# design.net
KiCad netlist of a schematic drawn in Altium Designer
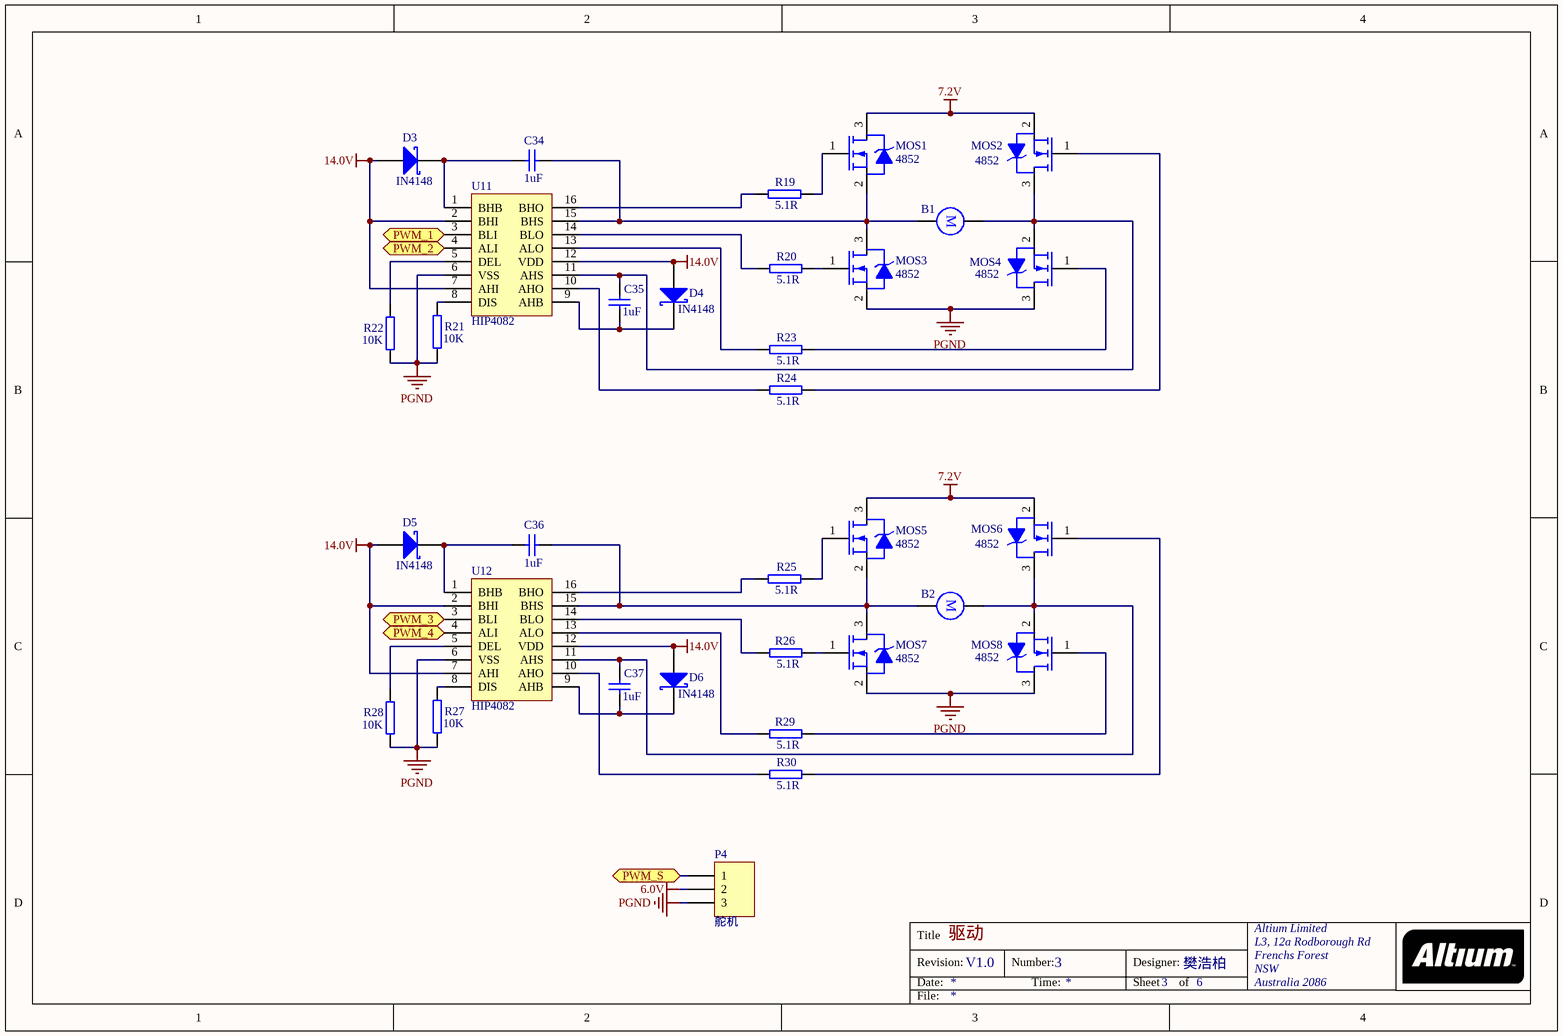
[diagram p0: 驱动.SchDoc]

(export (version "E")
  (design (tool "Eeschema 10.0.6"))
  (components
    (comp (ref "B1")
      (value "Motor")
      (footprint "Header-5.0-SMD")
      (fields (field (name "PUBLISHER") "Altium Limited"))
      (libsource (lib "Connectors") (part "Motor"))
    )
    (comp (ref "B2")
      (value "Motor")
      (footprint "Header-5.0-SMD")
      (fields (field (name "PUBLISHER") "Altium Limited"))
      (libsource (lib "Connectors") (part "Motor"))
    )
    (comp (ref "C34") (value "1uF") (footprint "CAP-0603") (libsource (lib "Connectors") (part "Cap")))
    (comp (ref "C35") (value "1uF") (footprint "CAP-0603") (libsource (lib "Connectors") (part "Cap")))
    (comp (ref "C36") (value "1uF") (footprint "CAP-0603") (libsource (lib "Connectors") (part "Cap")))
    (comp (ref "C37") (value "1uF") (footprint "CAP-0603") (libsource (lib "Connectors") (part "Cap")))
    (comp (ref "D3")
      (value "IN4148")
      (footprint "Diode-SMD-1206")
      (libsource (lib "Connectors") (part "Diode-Schottky"))
    )
    (comp (ref "D4")
      (value "IN4148")
      (footprint "Diode-SMD-1206")
      (libsource (lib "Connectors") (part "Diode-Schottky"))
    )
    (comp (ref "D5")
      (value "IN4148")
      (footprint "Diode-SMD-1206")
      (libsource (lib "Connectors") (part "Diode-Schottky"))
    )
    (comp (ref "D6")
      (value "IN4148")
      (footprint "Diode-SMD-1206")
      (libsource (lib "Connectors") (part "Diode-Schottky"))
    )
    (comp (ref "MOS1") (value "4852") (footprint "DFN-5_5X6MM") (libsource (lib "Devices") (part "N-MOS")))
    (comp (ref "MOS2") (value "4852") (footprint "DFN-5_5X6MM") (libsource (lib "Devices") (part "N-MOS")))
    (comp (ref "MOS3") (value "4852") (footprint "DFN-5_5X6MM") (libsource (lib "Devices") (part "N-MOS")))
    (comp (ref "MOS4") (value "4852") (footprint "DFN-5_5X6MM") (libsource (lib "Devices") (part "N-MOS")))
    (comp (ref "MOS5") (value "4852") (footprint "DFN-5_5X6MM") (libsource (lib "Devices") (part "N-MOS")))
    (comp (ref "MOS6") (value "4852") (footprint "DFN-5_5X6MM") (libsource (lib "Devices") (part "N-MOS")))
    (comp (ref "MOS7") (value "4852") (footprint "DFN-5_5X6MM") (libsource (lib "Devices") (part "N-MOS")))
    (comp (ref "MOS8") (value "4852") (footprint "DFN-5_5X6MM") (libsource (lib "Devices") (part "N-MOS")))
    (comp (ref "P4")
      (value "舵机")
      (footprint "Pin-Header-2.54-Single-3")
      (libsource (lib "Connectors-Header") (part "CON-3X1"))
    )
    (comp (ref "R19") (value "5.1R") (footprint "RES-0603") (libsource (lib "Connectors") (part "Res")))
    (comp (ref "R20") (value "5.1R") (footprint "RES-0603") (libsource (lib "Connectors") (part "Res")))
    (comp (ref "R21") (value "10K") (footprint "RES-0603") (libsource (lib "Connectors") (part "Res")))
    (comp (ref "R22") (value "10K") (footprint "RES-0603") (libsource (lib "Connectors") (part "Res")))
    (comp (ref "R23") (value "5.1R") (footprint "RES-0603") (libsource (lib "Connectors") (part "Res")))
    (comp (ref "R24") (value "5.1R") (footprint "RES-0603") (libsource (lib "Connectors") (part "Res")))
    (comp (ref "R25") (value "5.1R") (footprint "RES-0603") (libsource (lib "Connectors") (part "Res")))
    (comp (ref "R26") (value "5.1R") (footprint "RES-0603") (libsource (lib "Connectors") (part "Res")))
    (comp (ref "R27") (value "10K") (footprint "RES-0603") (libsource (lib "Connectors") (part "Res")))
    (comp (ref "R28") (value "10K") (footprint "RES-0603") (libsource (lib "Connectors") (part "Res")))
    (comp (ref "R29") (value "5.1R") (footprint "RES-0603") (libsource (lib "Connectors") (part "Res")))
    (comp (ref "R30") (value "5.1R") (footprint "RES-0603") (libsource (lib "Connectors") (part "Res")))
    (comp (ref "U11") (value "HIP4082") (footprint "SOP-16") (libsource (lib "Devices") (part "HIP4082")))
    (comp (ref "U12") (value "HIP4082") (footprint "SOP-16") (libsource (lib "Devices") (part "HIP4082")))
  )
  (nets
    (net (code "1") (name "/PWM_1") (class "Default")
      (node (ref "U11") (pin "3") (pinfunction "BLI_3") (pintype "passive"))
    )
    (net (code "2") (name "/PWM_2") (class "Default")
      (node (ref "U11") (pin "4") (pinfunction "ALI_4") (pintype "passive"))
    )
    (net (code "3") (name "/PWM_3") (class "Default")
      (node (ref "U12") (pin "3") (pinfunction "BLI_3") (pintype "passive"))
    )
    (net (code "4") (name "/PWM_4") (class "Default")
      (node (ref "U12") (pin "4") (pinfunction "ALI_4") (pintype "passive"))
    )
    (net (code "5") (name "/PWM_S") (class "Default")
      (node (ref "P4") (pin "1") (pinfunction "1_1") (pintype "passive"))
    )
    (net (code "6") (name "6.0V") (class "Default")
      (node (ref "P4") (pin "2") (pinfunction "2_2") (pintype "passive"))
    )
    (net (code "7") (name "7.2V") (class "Default")
      (node (ref "MOS1") (pin "3") (pinfunction "D_3") (pintype "passive"))
      (node (ref "MOS2") (pin "2") (pinfunction "S_2") (pintype "passive"))
      (node (ref "MOS5") (pin "3") (pinfunction "D_3") (pintype "passive"))
      (node (ref "MOS6") (pin "2") (pinfunction "S_2") (pintype "passive"))
    )
    (net (code "8") (name "14.0V") (class "Default")
      (node (ref "D3") (pin "A") (pinfunction "A_A") (pintype "passive"))
      (node (ref "D4") (pin "A") (pinfunction "A_A") (pintype "passive"))
      (node (ref "D5") (pin "A") (pinfunction "A_A") (pintype "passive"))
      (node (ref "D6") (pin "A") (pinfunction "A_A") (pintype "passive"))
      (node (ref "U11") (pin "12") (pinfunction "VDD_12") (pintype "passive"))
      (node (ref "U11") (pin "2") (pinfunction "BHI_2") (pintype "passive"))
      (node (ref "U11") (pin "7") (pinfunction "AHI_7") (pintype "passive"))
      (node (ref "U12") (pin "12") (pinfunction "VDD_12") (pintype "passive"))
      (node (ref "U12") (pin "2") (pinfunction "BHI_2") (pintype "passive"))
      (node (ref "U12") (pin "7") (pinfunction "AHI_7") (pintype "passive"))
    )
    (net (code "9") (name "Net-(MOS1-G)") (class "Default")
      (node (ref "MOS1") (pin "1") (pinfunction "G_1") (pintype "passive"))
      (node (ref "R19") (pin "1") (pinfunction "1_1") (pintype "passive"))
    )
    (net (code "10") (name "Net-(MOS1-S)") (class "Default")
      (node (ref "B1") (pin "2") (pinfunction "2_2") (pintype "passive"))
      (node (ref "C34") (pin "1") (pinfunction "1_1") (pintype "passive"))
      (node (ref "MOS1") (pin "2") (pinfunction "S_2") (pintype "passive"))
      (node (ref "MOS3") (pin "3") (pinfunction "D_3") (pintype "passive"))
      (node (ref "U11") (pin "15") (pinfunction "BHS_15") (pintype "passive"))
    )
    (net (code "11") (name "Net-(MOS2-D)") (class "Default")
      (node (ref "B1") (pin "1") (pinfunction "1_1") (pintype "passive"))
      (node (ref "C35") (pin "1") (pinfunction "1_1") (pintype "passive"))
      (node (ref "MOS2") (pin "3") (pinfunction "D_3") (pintype "passive"))
      (node (ref "MOS4") (pin "2") (pinfunction "S_2") (pintype "passive"))
      (node (ref "U11") (pin "11") (pinfunction "AHS_11") (pintype "passive"))
    )
    (net (code "12") (name "Net-(MOS2-G)") (class "Default")
      (node (ref "MOS2") (pin "1") (pinfunction "G_1") (pintype "passive"))
      (node (ref "R24") (pin "1") (pinfunction "1_1") (pintype "passive"))
    )
    (net (code "13") (name "Net-(MOS3-G)") (class "Default")
      (node (ref "MOS3") (pin "1") (pinfunction "G_1") (pintype "passive"))
      (node (ref "R20") (pin "1") (pinfunction "1_1") (pintype "passive"))
    )
    (net (code "14") (name "Net-(MOS4-G)") (class "Default")
      (node (ref "MOS4") (pin "1") (pinfunction "G_1") (pintype "passive"))
      (node (ref "R23") (pin "1") (pinfunction "1_1") (pintype "passive"))
    )
    (net (code "15") (name "Net-(MOS5-G)") (class "Default")
      (node (ref "MOS5") (pin "1") (pinfunction "G_1") (pintype "passive"))
      (node (ref "R25") (pin "1") (pinfunction "1_1") (pintype "passive"))
    )
    (net (code "16") (name "Net-(MOS5-S)") (class "Default")
      (node (ref "B2") (pin "2") (pinfunction "2_2") (pintype "passive"))
      (node (ref "C36") (pin "1") (pinfunction "1_1") (pintype "passive"))
      (node (ref "MOS5") (pin "2") (pinfunction "S_2") (pintype "passive"))
      (node (ref "MOS7") (pin "3") (pinfunction "D_3") (pintype "passive"))
      (node (ref "U12") (pin "15") (pinfunction "BHS_15") (pintype "passive"))
    )
    (net (code "17") (name "Net-(MOS6-D)") (class "Default")
      (node (ref "B2") (pin "1") (pinfunction "1_1") (pintype "passive"))
      (node (ref "C37") (pin "1") (pinfunction "1_1") (pintype "passive"))
      (node (ref "MOS6") (pin "3") (pinfunction "D_3") (pintype "passive"))
      (node (ref "MOS8") (pin "2") (pinfunction "S_2") (pintype "passive"))
      (node (ref "U12") (pin "11") (pinfunction "AHS_11") (pintype "passive"))
    )
    (net (code "18") (name "Net-(MOS6-G)") (class "Default")
      (node (ref "MOS6") (pin "1") (pinfunction "G_1") (pintype "passive"))
      (node (ref "R30") (pin "1") (pinfunction "1_1") (pintype "passive"))
    )
    (net (code "19") (name "Net-(MOS7-G)") (class "Default")
      (node (ref "MOS7") (pin "1") (pinfunction "G_1") (pintype "passive"))
      (node (ref "R26") (pin "1") (pinfunction "1_1") (pintype "passive"))
    )
    (net (code "20") (name "Net-(MOS8-G)") (class "Default")
      (node (ref "MOS8") (pin "1") (pinfunction "G_1") (pintype "passive"))
      (node (ref "R29") (pin "1") (pinfunction "1_1") (pintype "passive"))
    )
    (net (code "21") (name "Net-(U11-AHB)") (class "Default")
      (node (ref "C35") (pin "2") (pinfunction "2_2") (pintype "passive"))
      (node (ref "D4") (pin "K") (pinfunction "K_K") (pintype "passive"))
      (node (ref "U11") (pin "9") (pinfunction "AHB_9") (pintype "passive"))
    )
    (net (code "22") (name "Net-(U11-AHO)") (class "Default")
      (node (ref "R24") (pin "2") (pinfunction "2_2") (pintype "passive"))
      (node (ref "U11") (pin "10") (pinfunction "AHO_10") (pintype "passive"))
    )
    (net (code "23") (name "Net-(U11-ALO)") (class "Default")
      (node (ref "R23") (pin "2") (pinfunction "2_2") (pintype "passive"))
      (node (ref "U11") (pin "13") (pinfunction "ALO_13") (pintype "passive"))
    )
    (net (code "24") (name "Net-(U11-BHB)") (class "Default")
      (node (ref "C34") (pin "2") (pinfunction "2_2") (pintype "passive"))
      (node (ref "D3") (pin "K") (pinfunction "K_K") (pintype "passive"))
      (node (ref "U11") (pin "1") (pinfunction "BHB_1") (pintype "passive"))
    )
    (net (code "25") (name "Net-(U11-BHO)") (class "Default")
      (node (ref "R19") (pin "2") (pinfunction "2_2") (pintype "passive"))
      (node (ref "U11") (pin "16") (pinfunction "BHO_16") (pintype "passive"))
    )
    (net (code "26") (name "Net-(U11-BLO)") (class "Default")
      (node (ref "R20") (pin "2") (pinfunction "2_2") (pintype "passive"))
      (node (ref "U11") (pin "14") (pinfunction "BLO_14") (pintype "passive"))
    )
    (net (code "27") (name "Net-(U11-DEL)") (class "Default")
      (node (ref "R22") (pin "2") (pinfunction "2_2") (pintype "passive"))
      (node (ref "U11") (pin "5") (pinfunction "DEL_5") (pintype "passive"))
    )
    (net (code "28") (name "Net-(U11-DIS)") (class "Default")
      (node (ref "R21") (pin "2") (pinfunction "2_2") (pintype "passive"))
      (node (ref "U11") (pin "8") (pinfunction "DIS_8") (pintype "passive"))
    )
    (net (code "29") (name "Net-(U12-AHB)") (class "Default")
      (node (ref "C37") (pin "2") (pinfunction "2_2") (pintype "passive"))
      (node (ref "D6") (pin "K") (pinfunction "K_K") (pintype "passive"))
      (node (ref "U12") (pin "9") (pinfunction "AHB_9") (pintype "passive"))
    )
    (net (code "30") (name "Net-(U12-AHO)") (class "Default")
      (node (ref "R30") (pin "2") (pinfunction "2_2") (pintype "passive"))
      (node (ref "U12") (pin "10") (pinfunction "AHO_10") (pintype "passive"))
    )
    (net (code "31") (name "Net-(U12-ALO)") (class "Default")
      (node (ref "R29") (pin "2") (pinfunction "2_2") (pintype "passive"))
      (node (ref "U12") (pin "13") (pinfunction "ALO_13") (pintype "passive"))
    )
    (net (code "32") (name "Net-(U12-BHB)") (class "Default")
      (node (ref "C36") (pin "2") (pinfunction "2_2") (pintype "passive"))
      (node (ref "D5") (pin "K") (pinfunction "K_K") (pintype "passive"))
      (node (ref "U12") (pin "1") (pinfunction "BHB_1") (pintype "passive"))
    )
    (net (code "33") (name "Net-(U12-BHO)") (class "Default")
      (node (ref "R25") (pin "2") (pinfunction "2_2") (pintype "passive"))
      (node (ref "U12") (pin "16") (pinfunction "BHO_16") (pintype "passive"))
    )
    (net (code "34") (name "Net-(U12-BLO)") (class "Default")
      (node (ref "R26") (pin "2") (pinfunction "2_2") (pintype "passive"))
      (node (ref "U12") (pin "14") (pinfunction "BLO_14") (pintype "passive"))
    )
    (net (code "35") (name "Net-(U12-DEL)") (class "Default")
      (node (ref "R28") (pin "2") (pinfunction "2_2") (pintype "passive"))
      (node (ref "U12") (pin "5") (pinfunction "DEL_5") (pintype "passive"))
    )
    (net (code "36") (name "Net-(U12-DIS)") (class "Default")
      (node (ref "R27") (pin "2") (pinfunction "2_2") (pintype "passive"))
      (node (ref "U12") (pin "8") (pinfunction "DIS_8") (pintype "passive"))
    )
    (net (code "37") (name "PGND") (class "Default")
      (node (ref "MOS3") (pin "2") (pinfunction "S_2") (pintype "passive"))
      (node (ref "MOS4") (pin "3") (pinfunction "D_3") (pintype "passive"))
      (node (ref "MOS7") (pin "2") (pinfunction "S_2") (pintype "passive"))
      (node (ref "MOS8") (pin "3") (pinfunction "D_3") (pintype "passive"))
      (node (ref "P4") (pin "3") (pinfunction "3_3") (pintype "passive"))
      (node (ref "R21") (pin "1") (pinfunction "1_1") (pintype "passive"))
      (node (ref "R22") (pin "1") (pinfunction "1_1") (pintype "passive"))
      (node (ref "R27") (pin "1") (pinfunction "1_1") (pintype "passive"))
      (node (ref "R28") (pin "1") (pinfunction "1_1") (pintype "passive"))
      (node (ref "U11") (pin "6") (pinfunction "VSS_6") (pintype "passive"))
      (node (ref "U12") (pin "6") (pinfunction "VSS_6") (pintype "passive"))
    )
  )
)
